# board_schematic.net
KiCad netlist of a schematic drawn in Altium Designer
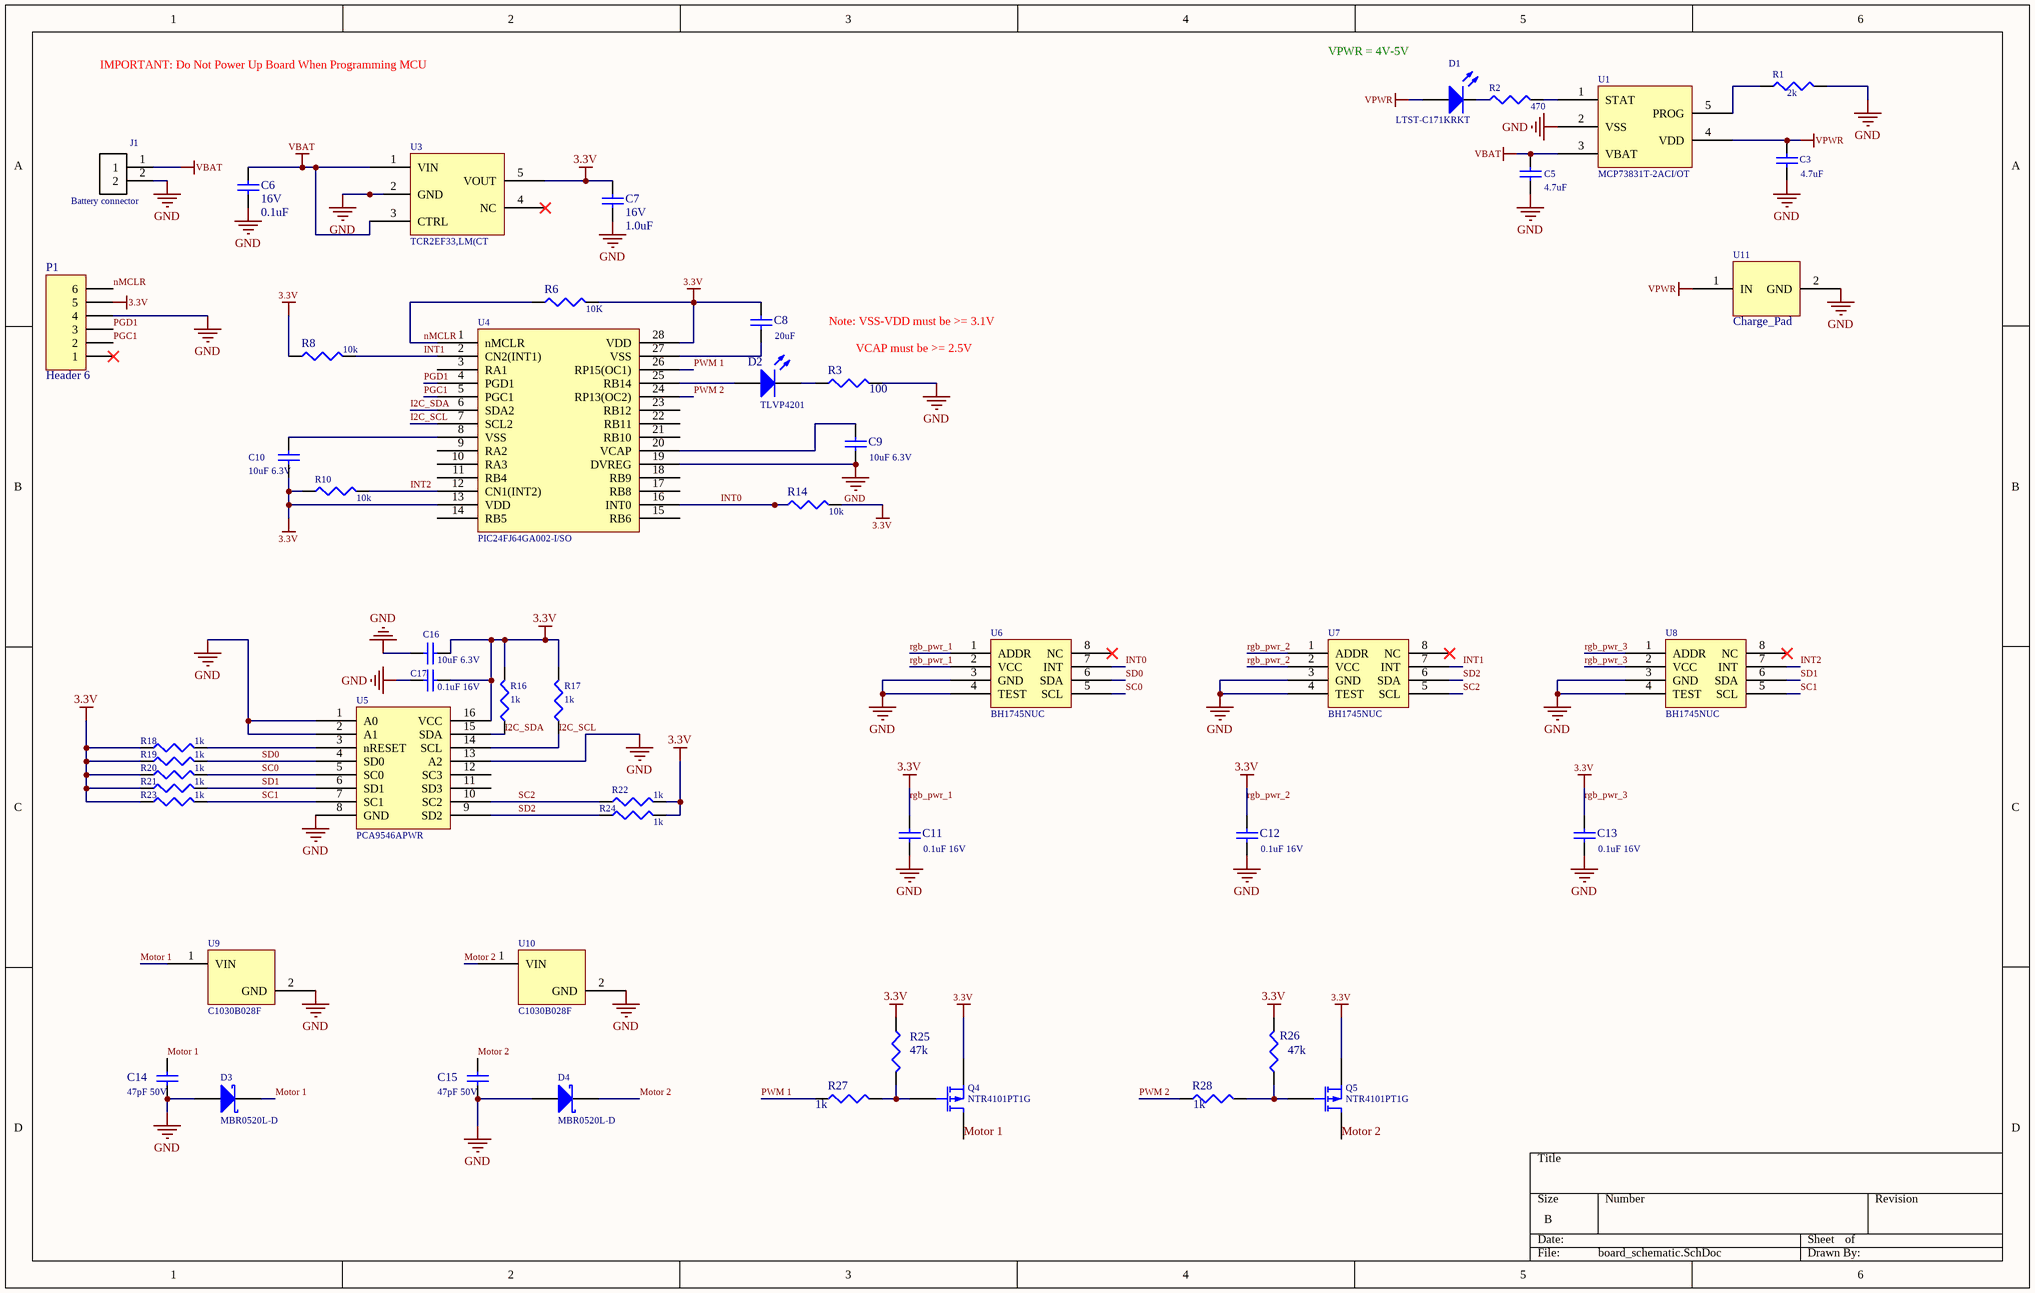
[diagram p0: board_schematic.SchDoc]

(export (version "E")
  (design (tool "Eeschema 10.0.6"))
  (components
    (comp (ref "C3")
      (value "4.7uF")
      (footprint "1608[0603]")
      (description "Capacitor (Semiconductor SIM Model)")
      (fields (field (name "Comment") "Cap Semi") (field (name "PUBLISHER") "Altium Limited"))
      (libsource (lib "Miscellaneous Devices") (part "Cap Semi"))
    )
    (comp (ref "C5")
      (value "4.7uF")
      (footprint "1608[0603]")
      (description "Capacitor (Semiconductor SIM Model)")
      (fields (field (name "Comment") "Cap Semi") (field (name "PUBLISHER") "Altium Limited"))
      (libsource (lib "Miscellaneous Devices") (part "Cap Semi"))
    )
    (comp (ref "C6")
      (value "16V")
      (footprint "1608[0603]")
      (description "Capacitor (Semiconductor SIM Model)")
      (fields (field (name "ALTIUM_VALUE") "0.1uF") (field (name "PUBLISHER") "Altium Limited"))
      (libsource (lib "Miscellaneous Devices") (part "Cap Semi"))
    )
    (comp (ref "C7")
      (value "16V")
      (footprint "1608[0603]")
      (description "Capacitor (Semiconductor SIM Model)")
      (fields (field (name "ALTIUM_VALUE") "1.0uF") (field (name "PUBLISHER") "Altium Limited"))
      (libsource (lib "Miscellaneous Devices") (part "Cap Semi"))
    )
    (comp (ref "C8")
      (value "20uF")
      (footprint "1608[0603]")
      (description "Capacitor (Semiconductor SIM Model)")
      (fields (field (name "Comment") "Cap Semi") (field (name "PUBLISHER") "Altium Limited"))
      (libsource (lib "Miscellaneous Devices") (part "Cap Semi"))
    )
    (comp (ref "C9")
      (value "10uF 6.3V")
      (footprint "1608[0603]")
      (description "Capacitor (Semiconductor SIM Model)")
      (fields (field (name "Comment") "Cap Semi") (field (name "PUBLISHER") "Altium Limited"))
      (libsource (lib "Miscellaneous Devices") (part "Cap Semi"))
    )
    (comp (ref "C10")
      (value "10uF 6.3V")
      (footprint "1608[0603]")
      (description "Capacitor (Semiconductor SIM Model)")
      (fields (field (name "Comment") "Cap Semi") (field (name "PUBLISHER") "Altium Limited"))
      (libsource (lib "Miscellaneous Devices") (part "Cap Semi"))
    )
    (comp (ref "C11")
      (value "0.1uF 16V")
      (footprint "1608[0603]")
      (description "Capacitor (Semiconductor SIM Model)")
      (fields (field (name "Comment") "Cap Semi") (field (name "PUBLISHER") "Altium Limited"))
      (libsource (lib "Miscellaneous Devices") (part "Cap Semi"))
    )
    (comp (ref "C12")
      (value "0.1uF 16V")
      (footprint "1608[0603]")
      (description "Capacitor (Semiconductor SIM Model)")
      (fields (field (name "Comment") "Cap Semi") (field (name "PUBLISHER") "Altium Limited"))
      (libsource (lib "Miscellaneous Devices") (part "Cap Semi"))
    )
    (comp (ref "C13")
      (value "0.1uF 16V")
      (footprint "1608[0603]")
      (description "Capacitor (Semiconductor SIM Model)")
      (fields (field (name "Comment") "Cap Semi") (field (name "PUBLISHER") "Altium Limited"))
      (libsource (lib "Miscellaneous Devices") (part "Cap Semi"))
    )
    (comp (ref "C14")
      (value "47pF 50V")
      (footprint "1608[0603]")
      (description "Capacitor (Semiconductor SIM Model)")
      (fields (field (name "Comment") "Cap Semi") (field (name "PUBLISHER") "Altium Limited"))
      (libsource (lib "Miscellaneous Devices") (part "Cap Semi"))
    )
    (comp (ref "C15")
      (value "47pF 50V")
      (footprint "1608[0603]")
      (description "Capacitor (Semiconductor SIM Model)")
      (fields (field (name "Comment") "Cap Semi") (field (name "PUBLISHER") "Altium Limited"))
      (libsource (lib "Miscellaneous Devices") (part "Cap Semi"))
    )
    (comp (ref "C16")
      (value "10uF 6.3V")
      (footprint "1608[0603]")
      (description "Capacitor (Semiconductor SIM Model)")
      (fields (field (name "Comment") "Cap Semi") (field (name "PUBLISHER") "Altium Limited"))
      (libsource (lib "Miscellaneous Devices") (part "Cap Semi"))
    )
    (comp (ref "C17")
      (value "0.1uF 16V")
      (footprint "1608[0603]")
      (description "Capacitor (Semiconductor SIM Model)")
      (fields (field (name "Comment") "Cap Semi") (field (name "PUBLISHER") "Altium Limited"))
      (libsource (lib "Miscellaneous Devices") (part "Cap Semi"))
    )
    (comp (ref "D1")
      (value "LTST-C171KRKT")
      (footprint "LED_pcb")
      (description "Typical RED, GREEN, YELLOW, AMBER GaAs LED")
      (fields (field (name "PUBLISHER") "Altium Limited"))
      (libsource (lib "Miscellaneous Devices") (part "LED2"))
    )
    (comp (ref "D2")
      (value "TLVP4201")
      (footprint "HDR1X2")
      (description "Typical INFRARED GaAs LED")
      (fields (field (name "PUBLISHER") "Altium Limited"))
      (libsource (lib "Miscellaneous Devices") (part "LED0"))
    )
    (comp (ref "D3")
      (value "MBR0520L-D")
      (footprint "SODFL375X128-2N")
      (description "Schottky Diode")
      (fields (field (name "PUBLISHER") "Altium Limited"))
      (libsource (lib "Miscellaneous Devices") (part "D Schottky"))
    )
    (comp (ref "D4")
      (value "MBR0520L-D")
      (footprint "SODFL375X128-2N")
      (description "Schottky Diode")
      (fields (field (name "PUBLISHER") "Altium Limited"))
      (libsource (lib "Miscellaneous Devices") (part "D Schottky"))
    )
    (comp (ref "J1")
      (value "Battery connector")
      (footprint "JST_S2B-PH-K-S(LF)(SN)")
      (description "PH Series 2 Position 2.0 mm Through Hole Side Entry Shrouded Header")
      (fields (field (name "MP") "S2B-PH-K-S_LF__SN_") (field (name "DIGI-KEY_PART_NUMBER") "455-1719-ND"))
      (libsource (lib "S2B-PH-K-S_LF__SN_") (part "S2B-PH-K-S(LF)(SN)"))
    )
    (comp (ref "P1")
      (value "Header 6")
      (footprint "HDR1X6")
      (description "Header, 6-Pin")
      (fields (field (name "PUBLISHER") "Altium Limited"))
      (libsource (lib "Miscellaneous Connectors") (part "Header 6"))
    )
    (comp (ref "Q4")
      (value "NTR4101PT1G")
      (footprint "SOT95P290X111-3N")
      (description "P-Channel MOSFET")
      (fields (field (name "PUBLISHER") "Altium Limited"))
      (libsource (lib "Miscellaneous Devices") (part "MOSFET-P"))
    )
    (comp (ref "Q5")
      (value "NTR4101PT1G")
      (footprint "SOT95P290X111-3N")
      (description "P-Channel MOSFET")
      (fields (field (name "PUBLISHER") "Altium Limited"))
      (libsource (lib "Miscellaneous Devices") (part "MOSFET-P"))
    )
    (comp (ref "R1")
      (value "2k")
      (footprint "J1-0603")
      (description "Resistor")
      (fields (field (name "Comment") "Res3") (field (name "PUBLISHER") "Altium Limited"))
      (libsource (lib "Miscellaneous Devices") (part "Res3"))
    )
    (comp (ref "R2")
      (value "470")
      (footprint "J1-0603")
      (description "Resistor")
      (fields (field (name "Comment") "Res3") (field (name "PUBLISHER") "Altium Limited"))
      (libsource (lib "Miscellaneous Devices") (part "Res3"))
    )
    (comp (ref "R3")
      (value "100")
      (footprint "J1-0603")
      (description "Resistor")
      (fields (field (name "Comment") "Res3") (field (name "PUBLISHER") "Altium Limited"))
      (libsource (lib "Miscellaneous Devices") (part "Res3"))
    )
    (comp (ref "R6")
      (value "10K")
      (footprint "J1-0603")
      (description "Resistor")
      (fields (field (name "Comment") "Res3") (field (name "PUBLISHER") "Altium Limited"))
      (libsource (lib "Miscellaneous Devices") (part "Res3"))
    )
    (comp (ref "R8")
      (value "10k")
      (footprint "J1-0603")
      (description "Resistor")
      (fields (field (name "Comment") "Res3") (field (name "PUBLISHER") "Altium Limited"))
      (libsource (lib "Miscellaneous Devices") (part "Res3"))
    )
    (comp (ref "R10")
      (value "10k")
      (footprint "J1-0603")
      (description "Resistor")
      (fields (field (name "Comment") "Res3") (field (name "PUBLISHER") "Altium Limited"))
      (libsource (lib "Miscellaneous Devices") (part "Res3"))
    )
    (comp (ref "R14")
      (value "10k")
      (footprint "J1-0603")
      (description "Resistor")
      (fields (field (name "Comment") "Res3") (field (name "PUBLISHER") "Altium Limited"))
      (libsource (lib "Miscellaneous Devices") (part "Res3"))
    )
    (comp (ref "R16")
      (value "1k")
      (footprint "J1-0603")
      (description "Resistor")
      (fields (field (name "PUBLISHER") "Altium Limited"))
      (libsource (lib "Miscellaneous Devices") (part "Res3"))
    )
    (comp (ref "R17")
      (value "1k")
      (footprint "J1-0603")
      (description "Resistor")
      (fields (field (name "PUBLISHER") "Altium Limited"))
      (libsource (lib "Miscellaneous Devices") (part "Res3"))
    )
    (comp (ref "R18")
      (value "1k")
      (footprint "J1-0603")
      (description "Resistor")
      (fields (field (name "PUBLISHER") "Altium Limited"))
      (libsource (lib "Miscellaneous Devices") (part "Res3"))
    )
    (comp (ref "R19")
      (value "1k")
      (footprint "J1-0603")
      (description "Resistor")
      (fields (field (name "PUBLISHER") "Altium Limited"))
      (libsource (lib "Miscellaneous Devices") (part "Res3"))
    )
    (comp (ref "R20")
      (value "1k")
      (footprint "J1-0603")
      (description "Resistor")
      (fields (field (name "PUBLISHER") "Altium Limited"))
      (libsource (lib "Miscellaneous Devices") (part "Res3"))
    )
    (comp (ref "R21")
      (value "1k")
      (footprint "J1-0603")
      (description "Resistor")
      (fields (field (name "Comment") "Res3") (field (name "PUBLISHER") "Altium Limited"))
      (libsource (lib "Miscellaneous Devices") (part "Res3"))
    )
    (comp (ref "R22")
      (value "1k")
      (footprint "J1-0603")
      (description "Resistor")
      (fields (field (name "Comment") "Res3") (field (name "PUBLISHER") "Altium Limited"))
      (libsource (lib "Miscellaneous Devices") (part "Res3"))
    )
    (comp (ref "R23")
      (value "1k")
      (footprint "J1-0603")
      (description "Resistor")
      (fields (field (name "Comment") "Res3") (field (name "PUBLISHER") "Altium Limited"))
      (libsource (lib "Miscellaneous Devices") (part "Res3"))
    )
    (comp (ref "R24")
      (value "1k")
      (footprint "J1-0603")
      (description "Resistor")
      (fields (field (name "Comment") "Res3") (field (name "PUBLISHER") "Altium Limited"))
      (libsource (lib "Miscellaneous Devices") (part "Res3"))
    )
    (comp (ref "R25")
      (value "47k")
      (footprint "J1-0603")
      (description "Resistor")
      (fields (field (name "Comment") "Res3") (field (name "PUBLISHER") "Altium Limited"))
      (libsource (lib "Miscellaneous Devices") (part "Res3"))
    )
    (comp (ref "R26")
      (value "47k")
      (footprint "J1-0603")
      (description "Resistor")
      (fields (field (name "Comment") "Res3") (field (name "PUBLISHER") "Altium Limited"))
      (libsource (lib "Miscellaneous Devices") (part "Res3"))
    )
    (comp (ref "R27")
      (value "1k")
      (footprint "J1-0603")
      (description "Resistor")
      (fields (field (name "Comment") "Res3") (field (name "PUBLISHER") "Altium Limited"))
      (libsource (lib "Miscellaneous Devices") (part "Res3"))
    )
    (comp (ref "R28")
      (value "1k")
      (footprint "J1-0603")
      (description "Resistor")
      (fields (field (name "Comment") "Res3") (field (name "PUBLISHER") "Altium Limited"))
      (libsource (lib "Miscellaneous Devices") (part "Res3"))
    )
    (comp (ref "U1")
      (value "MCP73831T-2ACI/OT")
      (footprint "SOT95P270X145-5N")
      (libsource (lib "batt_charger") (part "Component_1"))
    )
    (comp (ref "U3")
      (value "TCR2EF33,LM(CT")
      (footprint "SOT95P275X111-5N")
      (libsource (lib "LDO_reg") (part "Component_1"))
    )
    (comp (ref "U4")
      (value "PIC24FJ64GA002-I/SO")
      (footprint "SOIC127P1030X265-28N")
      (libsource (lib "PIC24F_MCU") (part "Component_1"))
    )
    (comp (ref "U5")
      (value "PCA9546APWR")
      (footprint "PCA9546APWR")
      (libsource (lib "I2CBus") (part "Component_1"))
    )
    (comp (ref "U6")
      (value "BH1745NUC")
      (footprint "*UDFN-8")
      (libsource (lib "rgb_sensor") (part "Component_1"))
    )
    (comp (ref "U7")
      (value "BH1745NUC")
      (footprint "*UDFN-8")
      (libsource (lib "rgb_sensor") (part "Component_1"))
    )
    (comp (ref "U8")
      (value "BH1745NUC")
      (footprint "*UDFN-8")
      (libsource (lib "rgb_sensor") (part "Component_1"))
    )
    (comp (ref "U9")
      (value "C1030B028F")
      (footprint "PCBComponent_1")
      (libsource (lib "motor_pads") (part "Component_1"))
    )
    (comp (ref "U10")
      (value "C1030B028F")
      (footprint "PCBComponent_1")
      (libsource (lib "motor_pads") (part "Component_1"))
    )
    (comp (ref "U11")
      (value "Charge_Pad")
      (footprint "charge_pad")
      (libsource (lib "charge_pad") (part "Component_1"))
    )
  )
  (nets
    (net (code "1") (name "/I2C_SCL") (class "Default")
      (node (ref "R17") (pin "1") (pinfunction "1_1") (pintype "passive"))
      (node (ref "U4") (pin "7") (pinfunction "SCL2_7") (pintype "passive"))
      (node (ref "U5") (pin "14") (pinfunction "SCL_14") (pintype "passive"))
    )
    (net (code "2") (name "/I2C_SDA") (class "Default")
      (node (ref "R16") (pin "1") (pinfunction "1_1") (pintype "passive"))
      (node (ref "U4") (pin "6") (pinfunction "SDA2_6") (pintype "passive"))
      (node (ref "U5") (pin "15") (pinfunction "SDA_15") (pintype "passive"))
    )
    (net (code "3") (name "/INT0") (class "Default")
      (node (ref "R14") (pin "1") (pinfunction "1_1") (pintype "passive"))
      (node (ref "U4") (pin "16") (pinfunction "INT0_16") (pintype "passive"))
      (node (ref "U6") (pin "7") (pinfunction "INT_7") (pintype "passive"))
    )
    (net (code "4") (name "/INT1") (class "Default")
      (node (ref "R8") (pin "2") (pinfunction "2_2") (pintype "passive"))
      (node (ref "U4") (pin "2") (pinfunction "CN2(INT1)_2") (pintype "passive"))
      (node (ref "U7") (pin "7") (pinfunction "INT_7") (pintype "passive"))
    )
    (net (code "5") (name "/INT2") (class "Default")
      (node (ref "R10") (pin "2") (pinfunction "2_2") (pintype "passive"))
      (node (ref "U4") (pin "12") (pinfunction "CN1(INT2)_12") (pintype "passive"))
      (node (ref "U8") (pin "7") (pinfunction "INT_7") (pintype "passive"))
    )
    (net (code "6") (name "/Motor 1") (class "Default")
      (node (ref "C14") (pin "2") (pinfunction "2_2") (pintype "passive"))
      (node (ref "D3") (pin "2") (pinfunction "K_2") (pintype "passive"))
      (node (ref "Q4") (pin "1") (pinfunction "D_1") (pintype "passive"))
      (node (ref "U9") (pin "1") (pinfunction "VIN_1") (pintype "passive"))
    )
    (net (code "7") (name "/Motor 2") (class "Default")
      (node (ref "C15") (pin "2") (pinfunction "2_2") (pintype "passive"))
      (node (ref "D4") (pin "2") (pinfunction "K_2") (pintype "passive"))
      (node (ref "Q5") (pin "1") (pinfunction "D_1") (pintype "passive"))
      (node (ref "U10") (pin "1") (pinfunction "VIN_1") (pintype "passive"))
    )
    (net (code "8") (name "/PGC1") (class "Default")
      (node (ref "P1") (pin "2") (pinfunction "2_2") (pintype "passive"))
      (node (ref "U4") (pin "5") (pinfunction "PGC1_5") (pintype "passive"))
    )
    (net (code "9") (name "/PGD1") (class "Default")
      (node (ref "P1") (pin "3") (pinfunction "3_3") (pintype "passive"))
      (node (ref "U4") (pin "4") (pinfunction "PGD1_4") (pintype "passive"))
    )
    (net (code "10") (name "/PWM 1") (class "Default")
      (node (ref "R27") (pin "1") (pinfunction "1_1") (pintype "passive"))
      (node (ref "U4") (pin "26") (pinfunction "RP15(OC1)_26") (pintype "passive"))
    )
    (net (code "11") (name "/PWM 2") (class "Default")
      (node (ref "R28") (pin "1") (pinfunction "1_1") (pintype "passive"))
      (node (ref "U4") (pin "24") (pinfunction "RP13(OC2)_24") (pintype "passive"))
    )
    (net (code "12") (name "/SC0") (class "Default")
      (node (ref "R20") (pin "2") (pinfunction "2_2") (pintype "passive"))
      (node (ref "U5") (pin "5") (pinfunction "SC0_5") (pintype "passive"))
      (node (ref "U6") (pin "5") (pinfunction "SCL_5") (pintype "passive"))
    )
    (net (code "13") (name "/SC1") (class "Default")
      (node (ref "R23") (pin "2") (pinfunction "2_2") (pintype "passive"))
      (node (ref "U5") (pin "7") (pinfunction "SC1_7") (pintype "passive"))
      (node (ref "U8") (pin "5") (pinfunction "SCL_5") (pintype "passive"))
    )
    (net (code "14") (name "/SC2") (class "Default")
      (node (ref "R22") (pin "1") (pinfunction "1_1") (pintype "passive"))
      (node (ref "U5") (pin "10") (pinfunction "SC2_10") (pintype "passive"))
      (node (ref "U7") (pin "5") (pinfunction "SCL_5") (pintype "passive"))
    )
    (net (code "15") (name "/SD0") (class "Default")
      (node (ref "R19") (pin "2") (pinfunction "2_2") (pintype "passive"))
      (node (ref "U5") (pin "4") (pinfunction "SD0_4") (pintype "passive"))
      (node (ref "U6") (pin "6") (pinfunction "SDA_6") (pintype "passive"))
    )
    (net (code "16") (name "/SD1") (class "Default")
      (node (ref "R21") (pin "2") (pinfunction "2_2") (pintype "passive"))
      (node (ref "U5") (pin "6") (pinfunction "SD1_6") (pintype "passive"))
      (node (ref "U8") (pin "6") (pinfunction "SDA_6") (pintype "passive"))
    )
    (net (code "17") (name "/SD2") (class "Default")
      (node (ref "R24") (pin "1") (pinfunction "1_1") (pintype "passive"))
      (node (ref "U5") (pin "9") (pinfunction "SD2_9") (pintype "passive"))
      (node (ref "U7") (pin "6") (pinfunction "SDA_6") (pintype "passive"))
    )
    (net (code "18") (name "/nMCLR") (class "Default")
      (node (ref "P1") (pin "6") (pinfunction "6_6") (pintype "passive"))
      (node (ref "R6") (pin "1") (pinfunction "1_1") (pintype "passive"))
      (node (ref "U4") (pin "1") (pinfunction "nMCLR_1") (pintype "passive"))
    )
    (net (code "19") (name "3.3V") (class "Default")
      (node (ref "C10") (pin "1") (pinfunction "1_1") (pintype "passive"))
      (node (ref "C11") (pin "1") (pinfunction "1_1") (pintype "passive"))
      (node (ref "C12") (pin "2") (pinfunction "2_2") (pintype "passive"))
      (node (ref "C13") (pin "2") (pinfunction "2_2") (pintype "passive"))
      (node (ref "C16") (pin "2") (pinfunction "2_2") (pintype "passive"))
      (node (ref "C17") (pin "2") (pinfunction "2_2") (pintype "passive"))
      (node (ref "C7") (pin "2") (pinfunction "2_2") (pintype "passive"))
      (node (ref "C8") (pin "2") (pinfunction "2_2") (pintype "passive"))
      (node (ref "P1") (pin "5") (pinfunction "5_5") (pintype "passive"))
      (node (ref "Q4") (pin "3") (pinfunction "S_3") (pintype "passive"))
      (node (ref "Q5") (pin "3") (pinfunction "S_3") (pintype "passive"))
      (node (ref "R10") (pin "1") (pinfunction "1_1") (pintype "passive"))
      (node (ref "R14") (pin "2") (pinfunction "2_2") (pintype "passive"))
      (node (ref "R16") (pin "2") (pinfunction "2_2") (pintype "passive"))
      (node (ref "R17") (pin "2") (pinfunction "2_2") (pintype "passive"))
      (node (ref "R18") (pin "1") (pinfunction "1_1") (pintype "passive"))
      (node (ref "R19") (pin "1") (pinfunction "1_1") (pintype "passive"))
      (node (ref "R20") (pin "1") (pinfunction "1_1") (pintype "passive"))
      (node (ref "R21") (pin "1") (pinfunction "1_1") (pintype "passive"))
      (node (ref "R22") (pin "2") (pinfunction "2_2") (pintype "passive"))
      (node (ref "R23") (pin "1") (pinfunction "1_1") (pintype "passive"))
      (node (ref "R24") (pin "2") (pinfunction "2_2") (pintype "passive"))
      (node (ref "R25") (pin "1") (pinfunction "1_1") (pintype "passive"))
      (node (ref "R26") (pin "2") (pinfunction "2_2") (pintype "passive"))
      (node (ref "R6") (pin "2") (pinfunction "2_2") (pintype "passive"))
      (node (ref "R8") (pin "1") (pinfunction "1_1") (pintype "passive"))
      (node (ref "U3") (pin "5") (pinfunction "VOUT_5") (pintype "passive"))
      (node (ref "U4") (pin "13") (pinfunction "VDD_13") (pintype "passive"))
      (node (ref "U4") (pin "28") (pinfunction "VDD_28") (pintype "passive"))
      (node (ref "U5") (pin "16") (pinfunction "VCC_16") (pintype "passive"))
      (node (ref "U6") (pin "1") (pinfunction "ADDR_1") (pintype "passive"))
      (node (ref "U6") (pin "2") (pinfunction "VCC_2") (pintype "passive"))
      (node (ref "U7") (pin "1") (pinfunction "ADDR_1") (pintype "passive"))
      (node (ref "U7") (pin "2") (pinfunction "VCC_2") (pintype "passive"))
      (node (ref "U8") (pin "1") (pinfunction "ADDR_1") (pintype "passive"))
      (node (ref "U8") (pin "2") (pinfunction "VCC_2") (pintype "passive"))
    )
    (net (code "20") (name "GND") (class "Default")
      (node (ref "C11") (pin "2") (pinfunction "2_2") (pintype "passive"))
      (node (ref "C12") (pin "1") (pinfunction "1_1") (pintype "passive"))
      (node (ref "C13") (pin "1") (pinfunction "1_1") (pintype "passive"))
      (node (ref "C14") (pin "1") (pinfunction "1_1") (pintype "passive"))
      (node (ref "C15") (pin "1") (pinfunction "1_1") (pintype "passive"))
      (node (ref "C16") (pin "1") (pinfunction "1_1") (pintype "passive"))
      (node (ref "C17") (pin "1") (pinfunction "1_1") (pintype "passive"))
      (node (ref "C3") (pin "1") (pinfunction "1_1") (pintype "passive"))
      (node (ref "C5") (pin "1") (pinfunction "1_1") (pintype "passive"))
      (node (ref "C6") (pin "1") (pinfunction "1_1") (pintype "passive"))
      (node (ref "C7") (pin "1") (pinfunction "1_1") (pintype "passive"))
      (node (ref "C9") (pin "1") (pinfunction "1_1") (pintype "passive"))
      (node (ref "D3") (pin "1") (pinfunction "A_1") (pintype "passive"))
      (node (ref "D4") (pin "1") (pinfunction "A_1") (pintype "passive"))
      (node (ref "J1") (pin "2") (pinfunction "2_2") (pintype "passive"))
      (node (ref "P1") (pin "4") (pinfunction "4_4") (pintype "passive"))
      (node (ref "R1") (pin "2") (pinfunction "2_2") (pintype "passive"))
      (node (ref "R3") (pin "2") (pinfunction "2_2") (pintype "passive"))
      (node (ref "U1") (pin "2") (pinfunction "VSS_2") (pintype "passive"))
      (node (ref "U10") (pin "2") (pinfunction "GND_2") (pintype "passive"))
      (node (ref "U11") (pin "2") (pinfunction "GND_2") (pintype "passive"))
      (node (ref "U3") (pin "2") (pinfunction "GND_2") (pintype "passive"))
      (node (ref "U4") (pin "19") (pinfunction "DVREG_19") (pintype "passive"))
      (node (ref "U5") (pin "1") (pinfunction "A0_1") (pintype "passive"))
      (node (ref "U5") (pin "13") (pinfunction "A2_13") (pintype "passive"))
      (node (ref "U5") (pin "2") (pinfunction "A1_2") (pintype "passive"))
      (node (ref "U5") (pin "8") (pinfunction "GND_8") (pintype "passive"))
      (node (ref "U6") (pin "3") (pinfunction "GND_3") (pintype "passive"))
      (node (ref "U6") (pin "4") (pinfunction "TEST_4") (pintype "passive"))
      (node (ref "U7") (pin "3") (pinfunction "GND_3") (pintype "passive"))
      (node (ref "U7") (pin "4") (pinfunction "TEST_4") (pintype "passive"))
      (node (ref "U8") (pin "3") (pinfunction "GND_3") (pintype "passive"))
      (node (ref "U8") (pin "4") (pinfunction "TEST_4") (pintype "passive"))
      (node (ref "U9") (pin "2") (pinfunction "GND_2") (pintype "passive"))
    )
    (net (code "21") (name "Net-(C8-Pad1)") (class "Default")
      (node (ref "C8") (pin "1") (pinfunction "1_1") (pintype "passive"))
      (node (ref "U4") (pin "27") (pinfunction "VSS_27") (pintype "passive"))
    )
    (net (code "22") (name "Net-(C10-Pad2)") (class "Default")
      (node (ref "C10") (pin "2") (pinfunction "2_2") (pintype "passive"))
      (node (ref "U4") (pin "8") (pinfunction "VSS_8") (pintype "passive"))
    )
    (net (code "23") (name "Net-(D1-K)") (class "Default")
      (node (ref "D1") (pin "2") (pinfunction "K_2") (pintype "passive"))
      (node (ref "R2") (pin "1") (pinfunction "1_1") (pintype "passive"))
    )
    (net (code "24") (name "Net-(D2-A)") (class "Default")
      (node (ref "D2") (pin "1") (pinfunction "A_1") (pintype "passive"))
      (node (ref "U4") (pin "25") (pinfunction "RB14_25") (pintype "passive"))
    )
    (net (code "25") (name "Net-(D2-K)") (class "Default")
      (node (ref "D2") (pin "2") (pinfunction "K_2") (pintype "passive"))
      (node (ref "R3") (pin "1") (pinfunction "1_1") (pintype "passive"))
    )
    (net (code "26") (name "Net-(Q4-G)") (class "Default")
      (node (ref "Q4") (pin "2") (pinfunction "G_2") (pintype "passive"))
      (node (ref "R25") (pin "2") (pinfunction "2_2") (pintype "passive"))
      (node (ref "R27") (pin "2") (pinfunction "2_2") (pintype "passive"))
    )
    (net (code "27") (name "Net-(Q5-G)") (class "Default")
      (node (ref "Q5") (pin "2") (pinfunction "G_2") (pintype "passive"))
      (node (ref "R26") (pin "1") (pinfunction "1_1") (pintype "passive"))
      (node (ref "R28") (pin "2") (pinfunction "2_2") (pintype "passive"))
    )
    (net (code "28") (name "Net-(U1-PROG)") (class "Default")
      (node (ref "R1") (pin "1") (pinfunction "1_1") (pintype "passive"))
      (node (ref "U1") (pin "5") (pinfunction "PROG_5") (pintype "passive"))
    )
    (net (code "29") (name "Net-(U1-STAT)") (class "Default")
      (node (ref "R2") (pin "2") (pinfunction "2_2") (pintype "passive"))
      (node (ref "U1") (pin "1") (pinfunction "STAT_1") (pintype "passive"))
    )
    (net (code "30") (name "Net-(U4-VCAP)") (class "Default")
      (node (ref "C9") (pin "2") (pinfunction "2_2") (pintype "passive"))
      (node (ref "U4") (pin "20") (pinfunction "VCAP_20") (pintype "passive"))
    )
    (net (code "31") (name "Net-(U5-nRESET)") (class "Default")
      (node (ref "R18") (pin "2") (pinfunction "2_2") (pintype "passive"))
      (node (ref "U5") (pin "3") (pinfunction "nRESET_3") (pintype "passive"))
    )
    (net (code "32") (name "VBAT") (class "Default")
      (node (ref "C5") (pin "2") (pinfunction "2_2") (pintype "passive"))
      (node (ref "C6") (pin "2") (pinfunction "2_2") (pintype "passive"))
      (node (ref "J1") (pin "1") (pinfunction "1_1") (pintype "passive"))
      (node (ref "U1") (pin "3") (pinfunction "VBAT_3") (pintype "passive"))
      (node (ref "U3") (pin "1") (pinfunction "VIN_1") (pintype "passive"))
      (node (ref "U3") (pin "3") (pinfunction "CTRL_3") (pintype "passive"))
    )
    (net (code "33") (name "VPWR") (class "Default")
      (node (ref "C3") (pin "2") (pinfunction "2_2") (pintype "passive"))
      (node (ref "D1") (pin "1") (pinfunction "A_1") (pintype "passive"))
      (node (ref "U1") (pin "4") (pinfunction "VDD_4") (pintype "passive"))
      (node (ref "U11") (pin "1") (pinfunction "IN_1") (pintype "passive"))
    )
    (net (code "34") (name "unconnected-(P1-Pad1)") (class "Default")
      (node (ref "P1") (pin "1") (pinfunction "1_1") (pintype "passive+no_connect"))
    )
    (net (code "35") (name "unconnected-(U3-NC-Pad4)") (class "Default")
      (node (ref "U3") (pin "4") (pinfunction "NC_4") (pintype "passive+no_connect"))
    )
    (net (code "36") (name "unconnected-(U4-RA1-Pad3)") (class "Default")
      (node (ref "U4") (pin "3") (pinfunction "RA1_3") (pintype "passive"))
    )
    (net (code "37") (name "unconnected-(U4-RA2-Pad9)") (class "Default")
      (node (ref "U4") (pin "9") (pinfunction "RA2_9") (pintype "passive"))
    )
    (net (code "38") (name "unconnected-(U4-RA3-Pad10)") (class "Default")
      (node (ref "U4") (pin "10") (pinfunction "RA3_10") (pintype "passive"))
    )
    (net (code "39") (name "unconnected-(U4-RB4-Pad11)") (class "Default")
      (node (ref "U4") (pin "11") (pinfunction "RB4_11") (pintype "passive"))
    )
    (net (code "40") (name "unconnected-(U4-RB5-Pad14)") (class "Default")
      (node (ref "U4") (pin "14") (pinfunction "RB5_14") (pintype "passive"))
    )
    (net (code "41") (name "unconnected-(U4-RB6-Pad15)") (class "Default")
      (node (ref "U4") (pin "15") (pinfunction "RB6_15") (pintype "passive"))
    )
    (net (code "42") (name "unconnected-(U4-RB8-Pad17)") (class "Default")
      (node (ref "U4") (pin "17") (pinfunction "RB8_17") (pintype "passive"))
    )
    (net (code "43") (name "unconnected-(U4-RB9-Pad18)") (class "Default")
      (node (ref "U4") (pin "18") (pinfunction "RB9_18") (pintype "passive"))
    )
    (net (code "44") (name "unconnected-(U4-RB10-Pad21)") (class "Default")
      (node (ref "U4") (pin "21") (pinfunction "RB10_21") (pintype "passive"))
    )
    (net (code "45") (name "unconnected-(U4-RB11-Pad22)") (class "Default")
      (node (ref "U4") (pin "22") (pinfunction "RB11_22") (pintype "passive"))
    )
    (net (code "46") (name "unconnected-(U4-RB12-Pad23)") (class "Default")
      (node (ref "U4") (pin "23") (pinfunction "RB12_23") (pintype "passive"))
    )
    (net (code "47") (name "unconnected-(U5-SC3-Pad12)") (class "Default")
      (node (ref "U5") (pin "12") (pinfunction "SC3_12") (pintype "passive"))
    )
    (net (code "48") (name "unconnected-(U5-SD3-Pad11)") (class "Default")
      (node (ref "U5") (pin "11") (pinfunction "SD3_11") (pintype "passive"))
    )
    (net (code "49") (name "unconnected-(U6-NC-Pad8)") (class "Default")
      (node (ref "U6") (pin "8") (pinfunction "NC_8") (pintype "passive+no_connect"))
    )
    (net (code "50") (name "unconnected-(U7-NC-Pad8)") (class "Default")
      (node (ref "U7") (pin "8") (pinfunction "NC_8") (pintype "passive+no_connect"))
    )
    (net (code "51") (name "unconnected-(U8-NC-Pad8)") (class "Default")
      (node (ref "U8") (pin "8") (pinfunction "NC_8") (pintype "passive+no_connect"))
    )
  )
)
